# main_board.net
KiCad netlist of a schematic drawn in EAGLE
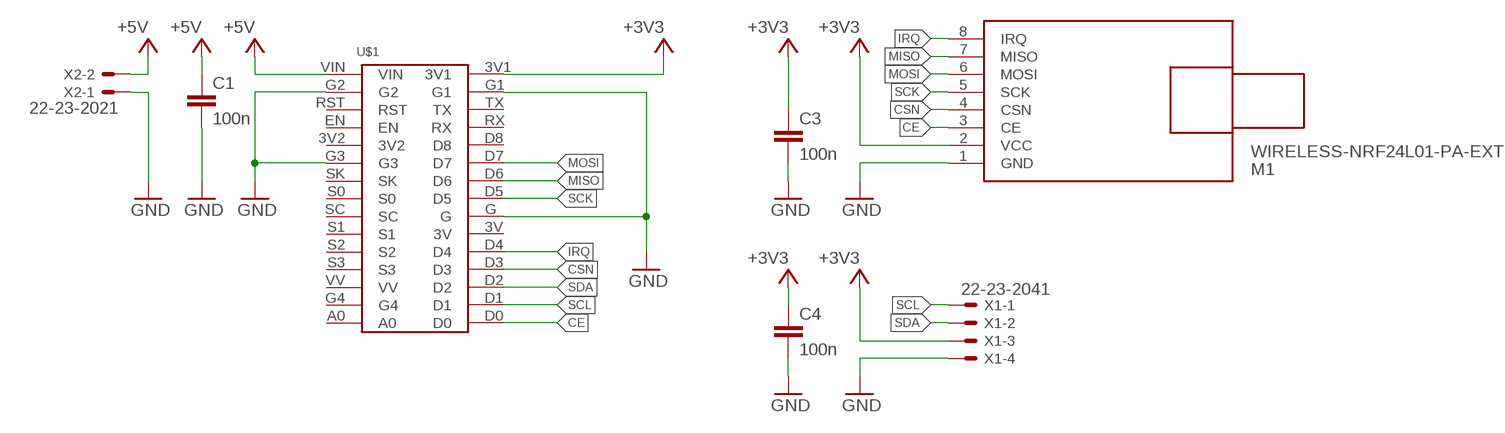
[diagram p0: schematic, sheet 1]

(export (version "E")
  (design (tool "Eeschema 10.0.6"))
  (components
    (comp (ref "C1")
      (value "100n")
      (footprint "eagle-import:C0805")
      (libsource (lib "eagle-import") (part "C-EUC0805"))
    )
    (comp (ref "C3")
      (value "100n")
      (footprint "eagle-import:C0805")
      (libsource (lib "eagle-import") (part "C-EUC0805"))
    )
    (comp (ref "C4")
      (value "100n")
      (footprint "eagle-import:C0805")
      (libsource (lib "eagle-import") (part "C-EUC0805"))
    )
    (comp (ref "M1")
      (value "WIRELESS-NRF24L01-PA-EXT")
      (footprint "eagle-import:WIRELESS-NRF24L01-PA-EXT")
      (libsource (lib "eagle-import") (part "WIRELESS-NRF24L01-PA-EXT"))
    )
    (comp (ref "U$1")
      (value "LOLIN")
      (footprint "eagle-import:LOLIN")
      (libsource (lib "eagle-import") (part "LOLIN"))
    )
    (comp (ref "X1")
      (value "22-23-2041")
      (footprint "eagle-import:22-23-2041")
      (fields (field (name "MF") "MOLEX"))
      (libsource (lib "eagle-import") (part "22-23-2041"))
    )
    (comp (ref "X2")
      (value "22-23-2021")
      (footprint "eagle-import:22-23-2021")
      (fields (field (name "MF") "MOLEX"))
      (libsource (lib "eagle-import") (part "22-23-2021"))
    )
  )
  (nets
    (net (code "1") (name "+3V3") (class "Default")
      (node (ref "C3") (pin "1") (pinfunction "1_1") (pintype "passive"))
      (node (ref "C4") (pin "1") (pinfunction "1_1") (pintype "passive"))
      (node (ref "M1") (pin "2") (pinfunction "VCC_2") (pintype "power_in"))
      (node (ref "U$1") (pin "3V1") (pinfunction "3V1_3V1") (pintype "bidirectional"))
      (node (ref "X1") (pin "3") (pinfunction "S_3") (pintype "passive"))
    )
    (net (code "2") (name "+5V") (class "Default")
      (node (ref "C1") (pin "1") (pinfunction "1_1") (pintype "passive"))
      (node (ref "U$1") (pin "VIN") (pinfunction "VIN_VIN") (pintype "bidirectional"))
      (node (ref "X2") (pin "2") (pinfunction "S_2") (pintype "passive"))
    )
    (net (code "3") (name "CE") (class "Default")
      (node (ref "M1") (pin "3") (pinfunction "CE_3") (pintype "bidirectional"))
      (node (ref "U$1") (pin "D0") (pinfunction "D0_D0") (pintype "bidirectional"))
    )
    (net (code "4") (name "CSN") (class "Default")
      (node (ref "M1") (pin "4") (pinfunction "CSN_4") (pintype "bidirectional"))
      (node (ref "U$1") (pin "D3") (pinfunction "D3_D3") (pintype "bidirectional"))
    )
    (net (code "5") (name "GND") (class "Default")
      (node (ref "C1") (pin "2") (pinfunction "2_2") (pintype "passive"))
      (node (ref "C3") (pin "2") (pinfunction "2_2") (pintype "passive"))
      (node (ref "C4") (pin "2") (pinfunction "2_2") (pintype "passive"))
      (node (ref "M1") (pin "1") (pinfunction "GND_1") (pintype "power_in"))
      (node (ref "U$1") (pin "G") (pinfunction "G_G") (pintype "bidirectional"))
      (node (ref "U$1") (pin "G1") (pinfunction "G1_G1") (pintype "bidirectional"))
      (node (ref "U$1") (pin "G2") (pinfunction "G2_G2") (pintype "bidirectional"))
      (node (ref "U$1") (pin "G3") (pinfunction "G3_G3") (pintype "bidirectional"))
      (node (ref "X1") (pin "4") (pinfunction "S_4") (pintype "passive"))
      (node (ref "X2") (pin "1") (pinfunction "S_1") (pintype "passive"))
    )
    (net (code "6") (name "IRQ") (class "Default")
      (node (ref "M1") (pin "8") (pinfunction "IRQ_8") (pintype "bidirectional"))
      (node (ref "U$1") (pin "D4") (pinfunction "D4_D4") (pintype "bidirectional"))
    )
    (net (code "7") (name "MISO") (class "Default")
      (node (ref "M1") (pin "7") (pinfunction "MISO_7") (pintype "bidirectional"))
      (node (ref "U$1") (pin "D6") (pinfunction "D6_D6") (pintype "bidirectional"))
    )
    (net (code "8") (name "MOSI") (class "Default")
      (node (ref "M1") (pin "6") (pinfunction "MOSI_6") (pintype "bidirectional"))
      (node (ref "U$1") (pin "D7") (pinfunction "D7_D7") (pintype "bidirectional"))
    )
    (net (code "9") (name "SCK") (class "Default")
      (node (ref "M1") (pin "5") (pinfunction "SCK_5") (pintype "bidirectional"))
      (node (ref "U$1") (pin "D5") (pinfunction "D5_D5") (pintype "bidirectional"))
    )
    (net (code "10") (name "SCL") (class "Default")
      (node (ref "U$1") (pin "D1") (pinfunction "D1_D1") (pintype "bidirectional"))
      (node (ref "X1") (pin "1") (pinfunction "S_1") (pintype "passive"))
    )
    (net (code "11") (name "SDA") (class "Default")
      (node (ref "U$1") (pin "D2") (pinfunction "D2_D2") (pintype "bidirectional"))
      (node (ref "X1") (pin "2") (pinfunction "S_2") (pintype "passive"))
    )
    (net (code "12") (name "unconnected-(U$1-Pad3V)") (class "Default")
      (node (ref "U$1") (pin "3V") (pinfunction "3V_3V") (pintype "bidirectional"))
    )
    (net (code "13") (name "unconnected-(U$1-Pad3V2)") (class "Default")
      (node (ref "U$1") (pin "3V2") (pinfunction "3V2_3V2") (pintype "bidirectional"))
    )
    (net (code "14") (name "unconnected-(U$1-PadA0)") (class "Default")
      (node (ref "U$1") (pin "A0") (pinfunction "A0_A0") (pintype "bidirectional"))
    )
    (net (code "15") (name "unconnected-(U$1-PadD8)") (class "Default")
      (node (ref "U$1") (pin "D8") (pinfunction "D8_D8") (pintype "bidirectional"))
    )
    (net (code "16") (name "unconnected-(U$1-PadEN)") (class "Default")
      (node (ref "U$1") (pin "EN") (pinfunction "EN_EN") (pintype "bidirectional"))
    )
    (net (code "17") (name "unconnected-(U$1-PadG4)") (class "Default")
      (node (ref "U$1") (pin "G4") (pinfunction "G4_G4") (pintype "bidirectional"))
    )
    (net (code "18") (name "unconnected-(U$1-PadRST)") (class "Default")
      (node (ref "U$1") (pin "RST") (pinfunction "RST_RST") (pintype "bidirectional"))
    )
    (net (code "19") (name "unconnected-(U$1-PadRX)") (class "Default")
      (node (ref "U$1") (pin "RX") (pinfunction "RX_RX") (pintype "bidirectional"))
    )
    (net (code "20") (name "unconnected-(U$1-PadS0)") (class "Default")
      (node (ref "U$1") (pin "S0") (pinfunction "S0_S0") (pintype "bidirectional"))
    )
    (net (code "21") (name "unconnected-(U$1-PadS1)") (class "Default")
      (node (ref "U$1") (pin "S1") (pinfunction "S1_S1") (pintype "bidirectional"))
    )
    (net (code "22") (name "unconnected-(U$1-PadS2)") (class "Default")
      (node (ref "U$1") (pin "S2") (pinfunction "S2_S2") (pintype "bidirectional"))
    )
    (net (code "23") (name "unconnected-(U$1-PadS3)") (class "Default")
      (node (ref "U$1") (pin "S3") (pinfunction "S3_S3") (pintype "bidirectional"))
    )
    (net (code "24") (name "unconnected-(U$1-PadSC)") (class "Default")
      (node (ref "U$1") (pin "SC") (pinfunction "SC_SC") (pintype "bidirectional"))
    )
    (net (code "25") (name "unconnected-(U$1-PadSK)") (class "Default")
      (node (ref "U$1") (pin "SK") (pinfunction "SK_SK") (pintype "bidirectional"))
    )
    (net (code "26") (name "unconnected-(U$1-PadTX)") (class "Default")
      (node (ref "U$1") (pin "TX") (pinfunction "TX_TX") (pintype "bidirectional"))
    )
    (net (code "27") (name "unconnected-(U$1-PadVV)") (class "Default")
      (node (ref "U$1") (pin "VV") (pinfunction "VV_VV") (pintype "bidirectional"))
    )
  )
)
